# bluetooth-shield.net
KiCad netlist of a schematic drawn in EAGLE
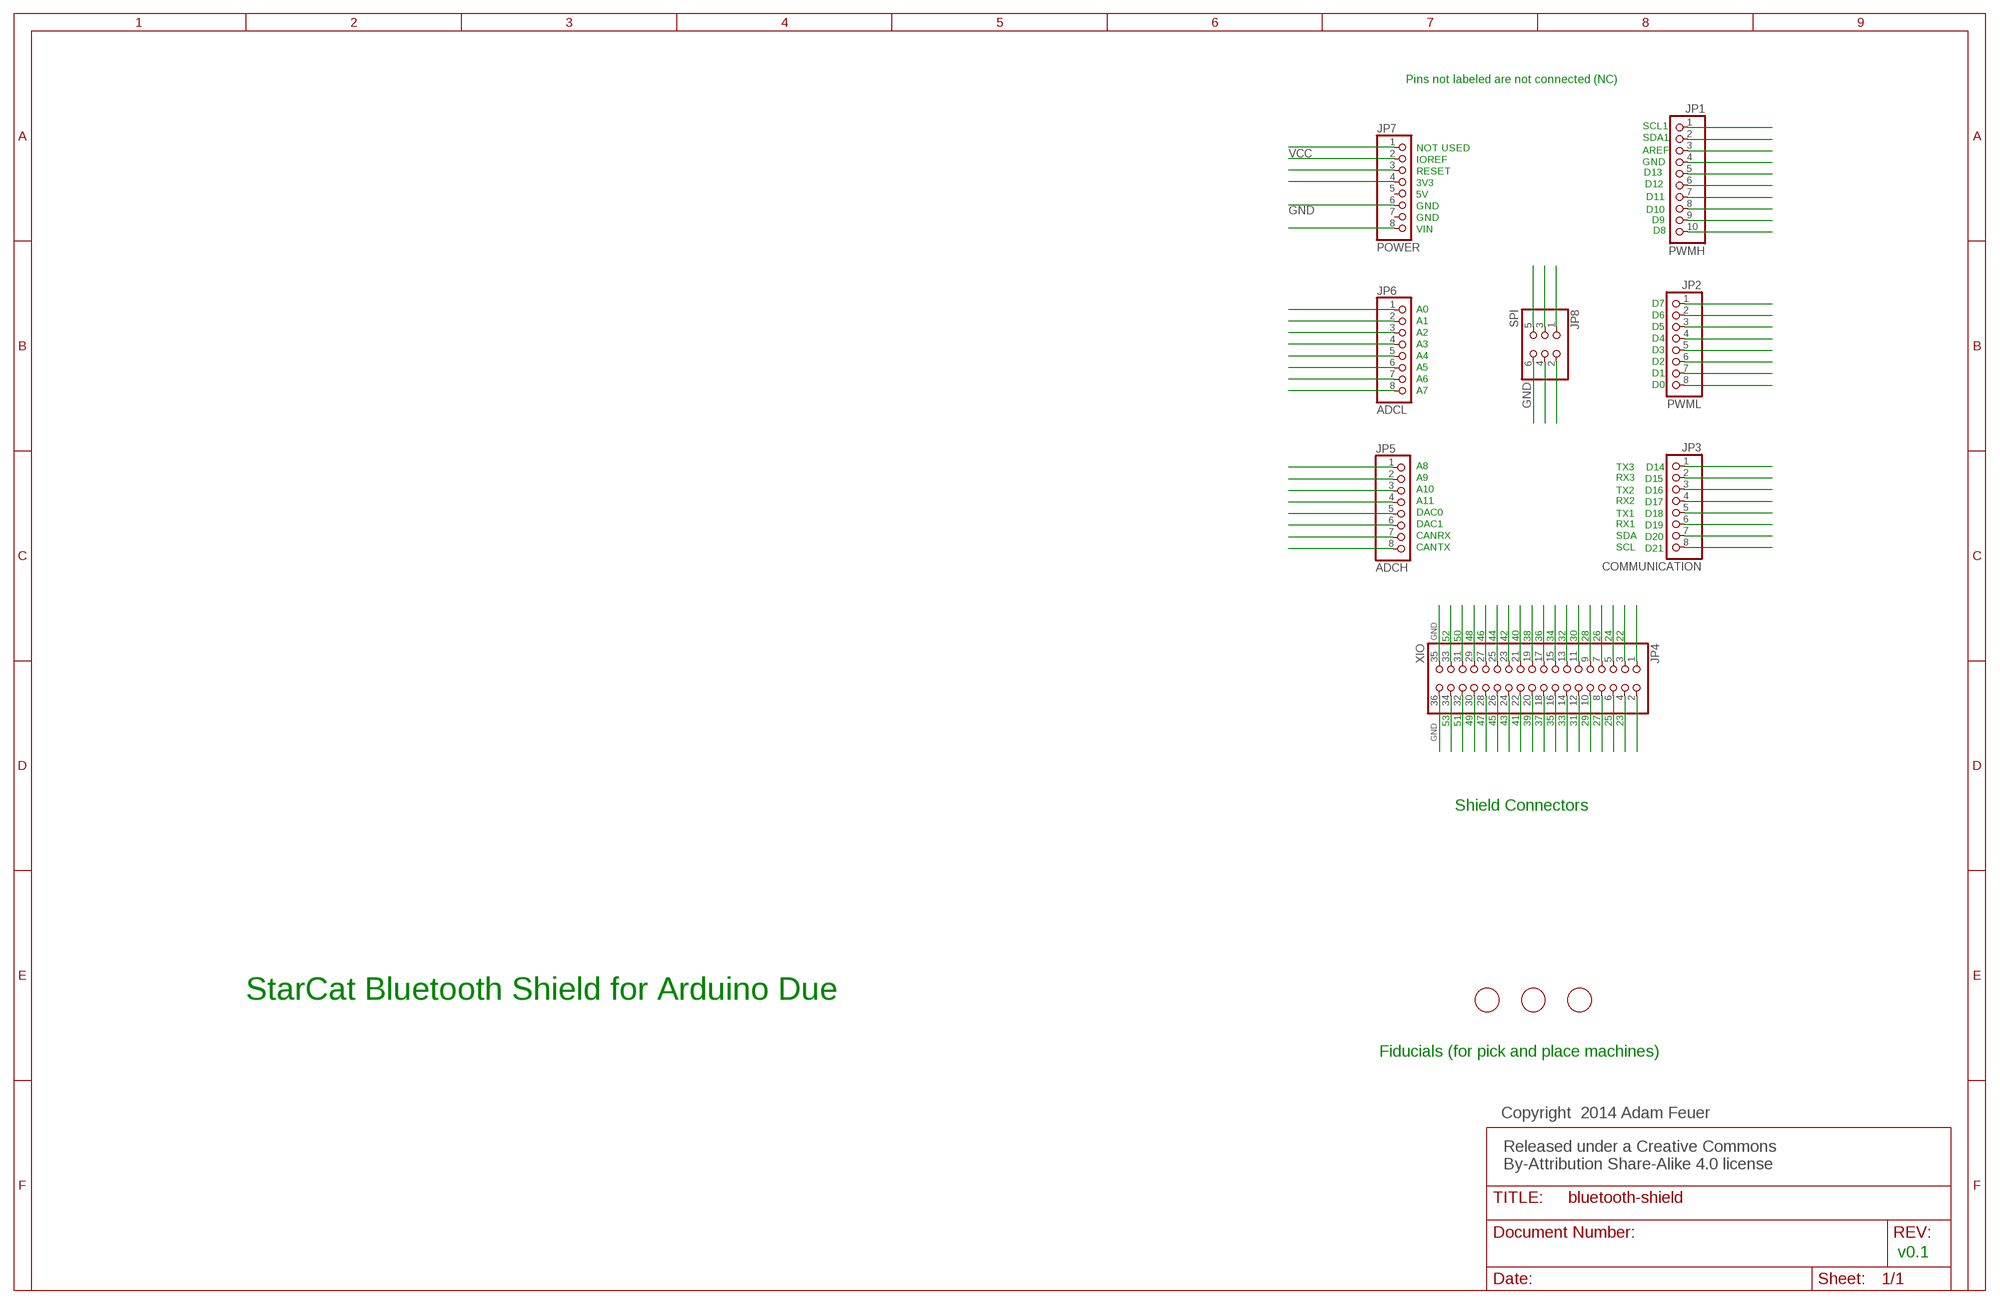
[diagram p0: schematic, sheet 1]

(export (version "E")
  (design (tool "Eeschema 10.0.6"))
  (components
    (comp (ref "JP1")
      (value "PWMH")
      (footprint "eagle-import:1X10")
      (libsource (lib "eagle-import") (part "PINHD-1X10"))
    )
    (comp (ref "JP2")
      (value "PWML")
      (footprint "eagle-import:1X08")
      (libsource (lib "eagle-import") (part "PINHD-1X8"))
    )
    (comp (ref "JP3")
      (value "COMMUNICATION")
      (footprint "eagle-import:1X08")
      (libsource (lib "eagle-import") (part "PINHD-1X8"))
    )
    (comp (ref "JP4")
      (value "XIO")
      (footprint "eagle-import:2X18")
      (libsource (lib "eagle-import") (part "PINHD-2X18"))
    )
    (comp (ref "JP5")
      (value "ADCH")
      (footprint "eagle-import:1X08")
      (libsource (lib "eagle-import") (part "PINHD-1X8"))
    )
    (comp (ref "JP6")
      (value "ADCL")
      (footprint "eagle-import:1X08")
      (libsource (lib "eagle-import") (part "PINHD-1X8"))
    )
    (comp (ref "JP7")
      (value "POWER")
      (footprint "eagle-import:1X08")
      (libsource (lib "eagle-import") (part "PINHD-1X8"))
    )
    (comp (ref "JP8")
      (value "SPI")
      (footprint "eagle-import:2X03")
      (libsource (lib "eagle-import") (part "PINHD-2X3"))
    )
    (comp (ref "U$2")
      (value "FIDUCIAL")
      (footprint "eagle-import:FIDUCIAL_1MM")
      (libsource (lib "eagle-import") (part "FIDUCIAL"))
    )
    (comp (ref "U$5")
      (value "FIDUCIAL")
      (footprint "eagle-import:FIDUCIAL_1MM")
      (libsource (lib "eagle-import") (part "FIDUCIAL"))
    )
    (comp (ref "U$6")
      (value "FIDUCIAL")
      (footprint "eagle-import:FIDUCIAL_1MM")
      (libsource (lib "eagle-import") (part "FIDUCIAL"))
    )
  )
  (nets
    (net (code "1") (name "/GND") (class "Default")
      (node (ref "JP4") (pin "35") (pinfunction "35_35") (pintype "passive"))
      (node (ref "JP4") (pin "36") (pinfunction "36_36") (pintype "passive"))
      (node (ref "JP8") (pin "6") (pinfunction "6_6") (pintype "passive"))
    )
    (net (code "2") (name "/VCC") (class "Default")
      (node (ref "JP7") (pin "2") (pinfunction "2_2") (pintype "passive"))
    )
    (net (code "3") (name "unconnected-(JP1-Pad1)") (class "Default")
      (node (ref "JP1") (pin "1") (pinfunction "1_1") (pintype "passive"))
    )
    (net (code "4") (name "unconnected-(JP1-Pad2)") (class "Default")
      (node (ref "JP1") (pin "2") (pinfunction "2_2") (pintype "passive"))
    )
    (net (code "5") (name "unconnected-(JP1-Pad3)") (class "Default")
      (node (ref "JP1") (pin "3") (pinfunction "3_3") (pintype "passive"))
    )
    (net (code "6") (name "unconnected-(JP1-Pad4)") (class "Default")
      (node (ref "JP1") (pin "4") (pinfunction "4_4") (pintype "passive"))
    )
    (net (code "7") (name "unconnected-(JP1-Pad5)") (class "Default")
      (node (ref "JP1") (pin "5") (pinfunction "5_5") (pintype "passive"))
    )
    (net (code "8") (name "unconnected-(JP1-Pad6)") (class "Default")
      (node (ref "JP1") (pin "6") (pinfunction "6_6") (pintype "passive"))
    )
    (net (code "9") (name "unconnected-(JP1-Pad7)") (class "Default")
      (node (ref "JP1") (pin "7") (pinfunction "7_7") (pintype "passive"))
    )
    (net (code "10") (name "unconnected-(JP1-Pad8)") (class "Default")
      (node (ref "JP1") (pin "8") (pinfunction "8_8") (pintype "passive"))
    )
    (net (code "11") (name "unconnected-(JP1-Pad9)") (class "Default")
      (node (ref "JP1") (pin "9") (pinfunction "9_9") (pintype "passive"))
    )
    (net (code "12") (name "unconnected-(JP1-Pad10)") (class "Default")
      (node (ref "JP1") (pin "10") (pinfunction "10_10") (pintype "passive"))
    )
    (net (code "13") (name "unconnected-(JP2-Pad1)") (class "Default")
      (node (ref "JP2") (pin "1") (pinfunction "1_1") (pintype "passive"))
    )
    (net (code "14") (name "unconnected-(JP2-Pad2)") (class "Default")
      (node (ref "JP2") (pin "2") (pinfunction "2_2") (pintype "passive"))
    )
    (net (code "15") (name "unconnected-(JP2-Pad3)") (class "Default")
      (node (ref "JP2") (pin "3") (pinfunction "3_3") (pintype "passive"))
    )
    (net (code "16") (name "unconnected-(JP2-Pad4)") (class "Default")
      (node (ref "JP2") (pin "4") (pinfunction "4_4") (pintype "passive"))
    )
    (net (code "17") (name "unconnected-(JP2-Pad5)") (class "Default")
      (node (ref "JP2") (pin "5") (pinfunction "5_5") (pintype "passive"))
    )
    (net (code "18") (name "unconnected-(JP2-Pad6)") (class "Default")
      (node (ref "JP2") (pin "6") (pinfunction "6_6") (pintype "passive"))
    )
    (net (code "19") (name "unconnected-(JP2-Pad7)") (class "Default")
      (node (ref "JP2") (pin "7") (pinfunction "7_7") (pintype "passive"))
    )
    (net (code "20") (name "unconnected-(JP2-Pad8)") (class "Default")
      (node (ref "JP2") (pin "8") (pinfunction "8_8") (pintype "passive"))
    )
    (net (code "21") (name "unconnected-(JP3-Pad1)") (class "Default")
      (node (ref "JP3") (pin "1") (pinfunction "1_1") (pintype "passive"))
    )
    (net (code "22") (name "unconnected-(JP3-Pad2)") (class "Default")
      (node (ref "JP3") (pin "2") (pinfunction "2_2") (pintype "passive"))
    )
    (net (code "23") (name "unconnected-(JP3-Pad3)") (class "Default")
      (node (ref "JP3") (pin "3") (pinfunction "3_3") (pintype "passive"))
    )
    (net (code "24") (name "unconnected-(JP3-Pad4)") (class "Default")
      (node (ref "JP3") (pin "4") (pinfunction "4_4") (pintype "passive"))
    )
    (net (code "25") (name "unconnected-(JP3-Pad5)") (class "Default")
      (node (ref "JP3") (pin "5") (pinfunction "5_5") (pintype "passive"))
    )
    (net (code "26") (name "unconnected-(JP3-Pad6)") (class "Default")
      (node (ref "JP3") (pin "6") (pinfunction "6_6") (pintype "passive"))
    )
    (net (code "27") (name "unconnected-(JP3-Pad7)") (class "Default")
      (node (ref "JP3") (pin "7") (pinfunction "7_7") (pintype "passive"))
    )
    (net (code "28") (name "unconnected-(JP3-Pad8)") (class "Default")
      (node (ref "JP3") (pin "8") (pinfunction "8_8") (pintype "passive"))
    )
    (net (code "29") (name "unconnected-(JP4-Pad1)") (class "Default")
      (node (ref "JP4") (pin "1") (pinfunction "1_1") (pintype "passive"))
    )
    (net (code "30") (name "unconnected-(JP4-Pad2)") (class "Default")
      (node (ref "JP4") (pin "2") (pinfunction "2_2") (pintype "passive"))
    )
    (net (code "31") (name "unconnected-(JP4-Pad3)") (class "Default")
      (node (ref "JP4") (pin "3") (pinfunction "3_3") (pintype "passive"))
    )
    (net (code "32") (name "unconnected-(JP4-Pad4)") (class "Default")
      (node (ref "JP4") (pin "4") (pinfunction "4_4") (pintype "passive"))
    )
    (net (code "33") (name "unconnected-(JP4-Pad5)") (class "Default")
      (node (ref "JP4") (pin "5") (pinfunction "5_5") (pintype "passive"))
    )
    (net (code "34") (name "unconnected-(JP4-Pad6)") (class "Default")
      (node (ref "JP4") (pin "6") (pinfunction "6_6") (pintype "passive"))
    )
    (net (code "35") (name "unconnected-(JP4-Pad7)") (class "Default")
      (node (ref "JP4") (pin "7") (pinfunction "7_7") (pintype "passive"))
    )
    (net (code "36") (name "unconnected-(JP4-Pad8)") (class "Default")
      (node (ref "JP4") (pin "8") (pinfunction "8_8") (pintype "passive"))
    )
    (net (code "37") (name "unconnected-(JP4-Pad9)") (class "Default")
      (node (ref "JP4") (pin "9") (pinfunction "9_9") (pintype "passive"))
    )
    (net (code "38") (name "unconnected-(JP4-Pad10)") (class "Default")
      (node (ref "JP4") (pin "10") (pinfunction "10_10") (pintype "passive"))
    )
    (net (code "39") (name "unconnected-(JP4-Pad11)") (class "Default")
      (node (ref "JP4") (pin "11") (pinfunction "11_11") (pintype "passive"))
    )
    (net (code "40") (name "unconnected-(JP4-Pad12)") (class "Default")
      (node (ref "JP4") (pin "12") (pinfunction "12_12") (pintype "passive"))
    )
    (net (code "41") (name "unconnected-(JP4-Pad13)") (class "Default")
      (node (ref "JP4") (pin "13") (pinfunction "13_13") (pintype "passive"))
    )
    (net (code "42") (name "unconnected-(JP4-Pad14)") (class "Default")
      (node (ref "JP4") (pin "14") (pinfunction "14_14") (pintype "passive"))
    )
    (net (code "43") (name "unconnected-(JP4-Pad15)") (class "Default")
      (node (ref "JP4") (pin "15") (pinfunction "15_15") (pintype "passive"))
    )
    (net (code "44") (name "unconnected-(JP4-Pad16)") (class "Default")
      (node (ref "JP4") (pin "16") (pinfunction "16_16") (pintype "passive"))
    )
    (net (code "45") (name "unconnected-(JP4-Pad17)") (class "Default")
      (node (ref "JP4") (pin "17") (pinfunction "17_17") (pintype "passive"))
    )
    (net (code "46") (name "unconnected-(JP4-Pad18)") (class "Default")
      (node (ref "JP4") (pin "18") (pinfunction "18_18") (pintype "passive"))
    )
    (net (code "47") (name "unconnected-(JP4-Pad19)") (class "Default")
      (node (ref "JP4") (pin "19") (pinfunction "19_19") (pintype "passive"))
    )
    (net (code "48") (name "unconnected-(JP4-Pad20)") (class "Default")
      (node (ref "JP4") (pin "20") (pinfunction "20_20") (pintype "passive"))
    )
    (net (code "49") (name "unconnected-(JP4-Pad21)") (class "Default")
      (node (ref "JP4") (pin "21") (pinfunction "21_21") (pintype "passive"))
    )
    (net (code "50") (name "unconnected-(JP4-Pad22)") (class "Default")
      (node (ref "JP4") (pin "22") (pinfunction "22_22") (pintype "passive"))
    )
    (net (code "51") (name "unconnected-(JP4-Pad23)") (class "Default")
      (node (ref "JP4") (pin "23") (pinfunction "23_23") (pintype "passive"))
    )
    (net (code "52") (name "unconnected-(JP4-Pad24)") (class "Default")
      (node (ref "JP4") (pin "24") (pinfunction "24_24") (pintype "passive"))
    )
    (net (code "53") (name "unconnected-(JP4-Pad25)") (class "Default")
      (node (ref "JP4") (pin "25") (pinfunction "25_25") (pintype "passive"))
    )
    (net (code "54") (name "unconnected-(JP4-Pad26)") (class "Default")
      (node (ref "JP4") (pin "26") (pinfunction "26_26") (pintype "passive"))
    )
    (net (code "55") (name "unconnected-(JP4-Pad27)") (class "Default")
      (node (ref "JP4") (pin "27") (pinfunction "27_27") (pintype "passive"))
    )
    (net (code "56") (name "unconnected-(JP4-Pad28)") (class "Default")
      (node (ref "JP4") (pin "28") (pinfunction "28_28") (pintype "passive"))
    )
    (net (code "57") (name "unconnected-(JP4-Pad29)") (class "Default")
      (node (ref "JP4") (pin "29") (pinfunction "29_29") (pintype "passive"))
    )
    (net (code "58") (name "unconnected-(JP4-Pad30)") (class "Default")
      (node (ref "JP4") (pin "30") (pinfunction "30_30") (pintype "passive"))
    )
    (net (code "59") (name "unconnected-(JP4-Pad31)") (class "Default")
      (node (ref "JP4") (pin "31") (pinfunction "31_31") (pintype "passive"))
    )
    (net (code "60") (name "unconnected-(JP4-Pad32)") (class "Default")
      (node (ref "JP4") (pin "32") (pinfunction "32_32") (pintype "passive"))
    )
    (net (code "61") (name "unconnected-(JP4-Pad33)") (class "Default")
      (node (ref "JP4") (pin "33") (pinfunction "33_33") (pintype "passive"))
    )
    (net (code "62") (name "unconnected-(JP4-Pad34)") (class "Default")
      (node (ref "JP4") (pin "34") (pinfunction "34_34") (pintype "passive"))
    )
    (net (code "63") (name "unconnected-(JP5-Pad1)") (class "Default")
      (node (ref "JP5") (pin "1") (pinfunction "1_1") (pintype "passive"))
    )
    (net (code "64") (name "unconnected-(JP5-Pad2)") (class "Default")
      (node (ref "JP5") (pin "2") (pinfunction "2_2") (pintype "passive"))
    )
    (net (code "65") (name "unconnected-(JP5-Pad3)") (class "Default")
      (node (ref "JP5") (pin "3") (pinfunction "3_3") (pintype "passive"))
    )
    (net (code "66") (name "unconnected-(JP5-Pad4)") (class "Default")
      (node (ref "JP5") (pin "4") (pinfunction "4_4") (pintype "passive"))
    )
    (net (code "67") (name "unconnected-(JP5-Pad5)") (class "Default")
      (node (ref "JP5") (pin "5") (pinfunction "5_5") (pintype "passive"))
    )
    (net (code "68") (name "unconnected-(JP5-Pad6)") (class "Default")
      (node (ref "JP5") (pin "6") (pinfunction "6_6") (pintype "passive"))
    )
    (net (code "69") (name "unconnected-(JP5-Pad7)") (class "Default")
      (node (ref "JP5") (pin "7") (pinfunction "7_7") (pintype "passive"))
    )
    (net (code "70") (name "unconnected-(JP5-Pad8)") (class "Default")
      (node (ref "JP5") (pin "8") (pinfunction "8_8") (pintype "passive"))
    )
    (net (code "71") (name "unconnected-(JP6-Pad1)") (class "Default")
      (node (ref "JP6") (pin "1") (pinfunction "1_1") (pintype "passive"))
    )
    (net (code "72") (name "unconnected-(JP6-Pad2)") (class "Default")
      (node (ref "JP6") (pin "2") (pinfunction "2_2") (pintype "passive"))
    )
    (net (code "73") (name "unconnected-(JP6-Pad3)") (class "Default")
      (node (ref "JP6") (pin "3") (pinfunction "3_3") (pintype "passive"))
    )
    (net (code "74") (name "unconnected-(JP6-Pad4)") (class "Default")
      (node (ref "JP6") (pin "4") (pinfunction "4_4") (pintype "passive"))
    )
    (net (code "75") (name "unconnected-(JP6-Pad5)") (class "Default")
      (node (ref "JP6") (pin "5") (pinfunction "5_5") (pintype "passive"))
    )
    (net (code "76") (name "unconnected-(JP6-Pad6)") (class "Default")
      (node (ref "JP6") (pin "6") (pinfunction "6_6") (pintype "passive"))
    )
    (net (code "77") (name "unconnected-(JP6-Pad7)") (class "Default")
      (node (ref "JP6") (pin "7") (pinfunction "7_7") (pintype "passive"))
    )
    (net (code "78") (name "unconnected-(JP6-Pad8)") (class "Default")
      (node (ref "JP6") (pin "8") (pinfunction "8_8") (pintype "passive"))
    )
    (net (code "79") (name "unconnected-(JP7-Pad1)") (class "Default")
      (node (ref "JP7") (pin "1") (pinfunction "1_1") (pintype "passive"))
    )
    (net (code "80") (name "unconnected-(JP7-Pad3)") (class "Default")
      (node (ref "JP7") (pin "3") (pinfunction "3_3") (pintype "passive"))
    )
    (net (code "81") (name "unconnected-(JP7-Pad4)") (class "Default")
      (node (ref "JP7") (pin "4") (pinfunction "4_4") (pintype "passive"))
    )
    (net (code "82") (name "unconnected-(JP7-Pad5)") (class "Default")
      (node (ref "JP7") (pin "5") (pinfunction "5_5") (pintype "passive"))
    )
    (net (code "83") (name "unconnected-(JP7-Pad6)") (class "Default")
      (node (ref "JP7") (pin "6") (pinfunction "6_6") (pintype "passive"))
    )
    (net (code "84") (name "unconnected-(JP7-Pad7)") (class "Default")
      (node (ref "JP7") (pin "7") (pinfunction "7_7") (pintype "passive"))
    )
    (net (code "85") (name "unconnected-(JP7-Pad8)") (class "Default")
      (node (ref "JP7") (pin "8") (pinfunction "8_8") (pintype "passive"))
    )
    (net (code "86") (name "unconnected-(JP8-Pad1)") (class "Default")
      (node (ref "JP8") (pin "1") (pinfunction "1_1") (pintype "passive"))
    )
    (net (code "87") (name "unconnected-(JP8-Pad2)") (class "Default")
      (node (ref "JP8") (pin "2") (pinfunction "2_2") (pintype "passive"))
    )
    (net (code "88") (name "unconnected-(JP8-Pad3)") (class "Default")
      (node (ref "JP8") (pin "3") (pinfunction "3_3") (pintype "passive"))
    )
    (net (code "89") (name "unconnected-(JP8-Pad4)") (class "Default")
      (node (ref "JP8") (pin "4") (pinfunction "4_4") (pintype "passive"))
    )
    (net (code "90") (name "unconnected-(JP8-Pad5)") (class "Default")
      (node (ref "JP8") (pin "5") (pinfunction "5_5") (pintype "passive"))
    )
  )
)
